# cypi.net
KiCad netlist of a schematic drawn in EAGLE
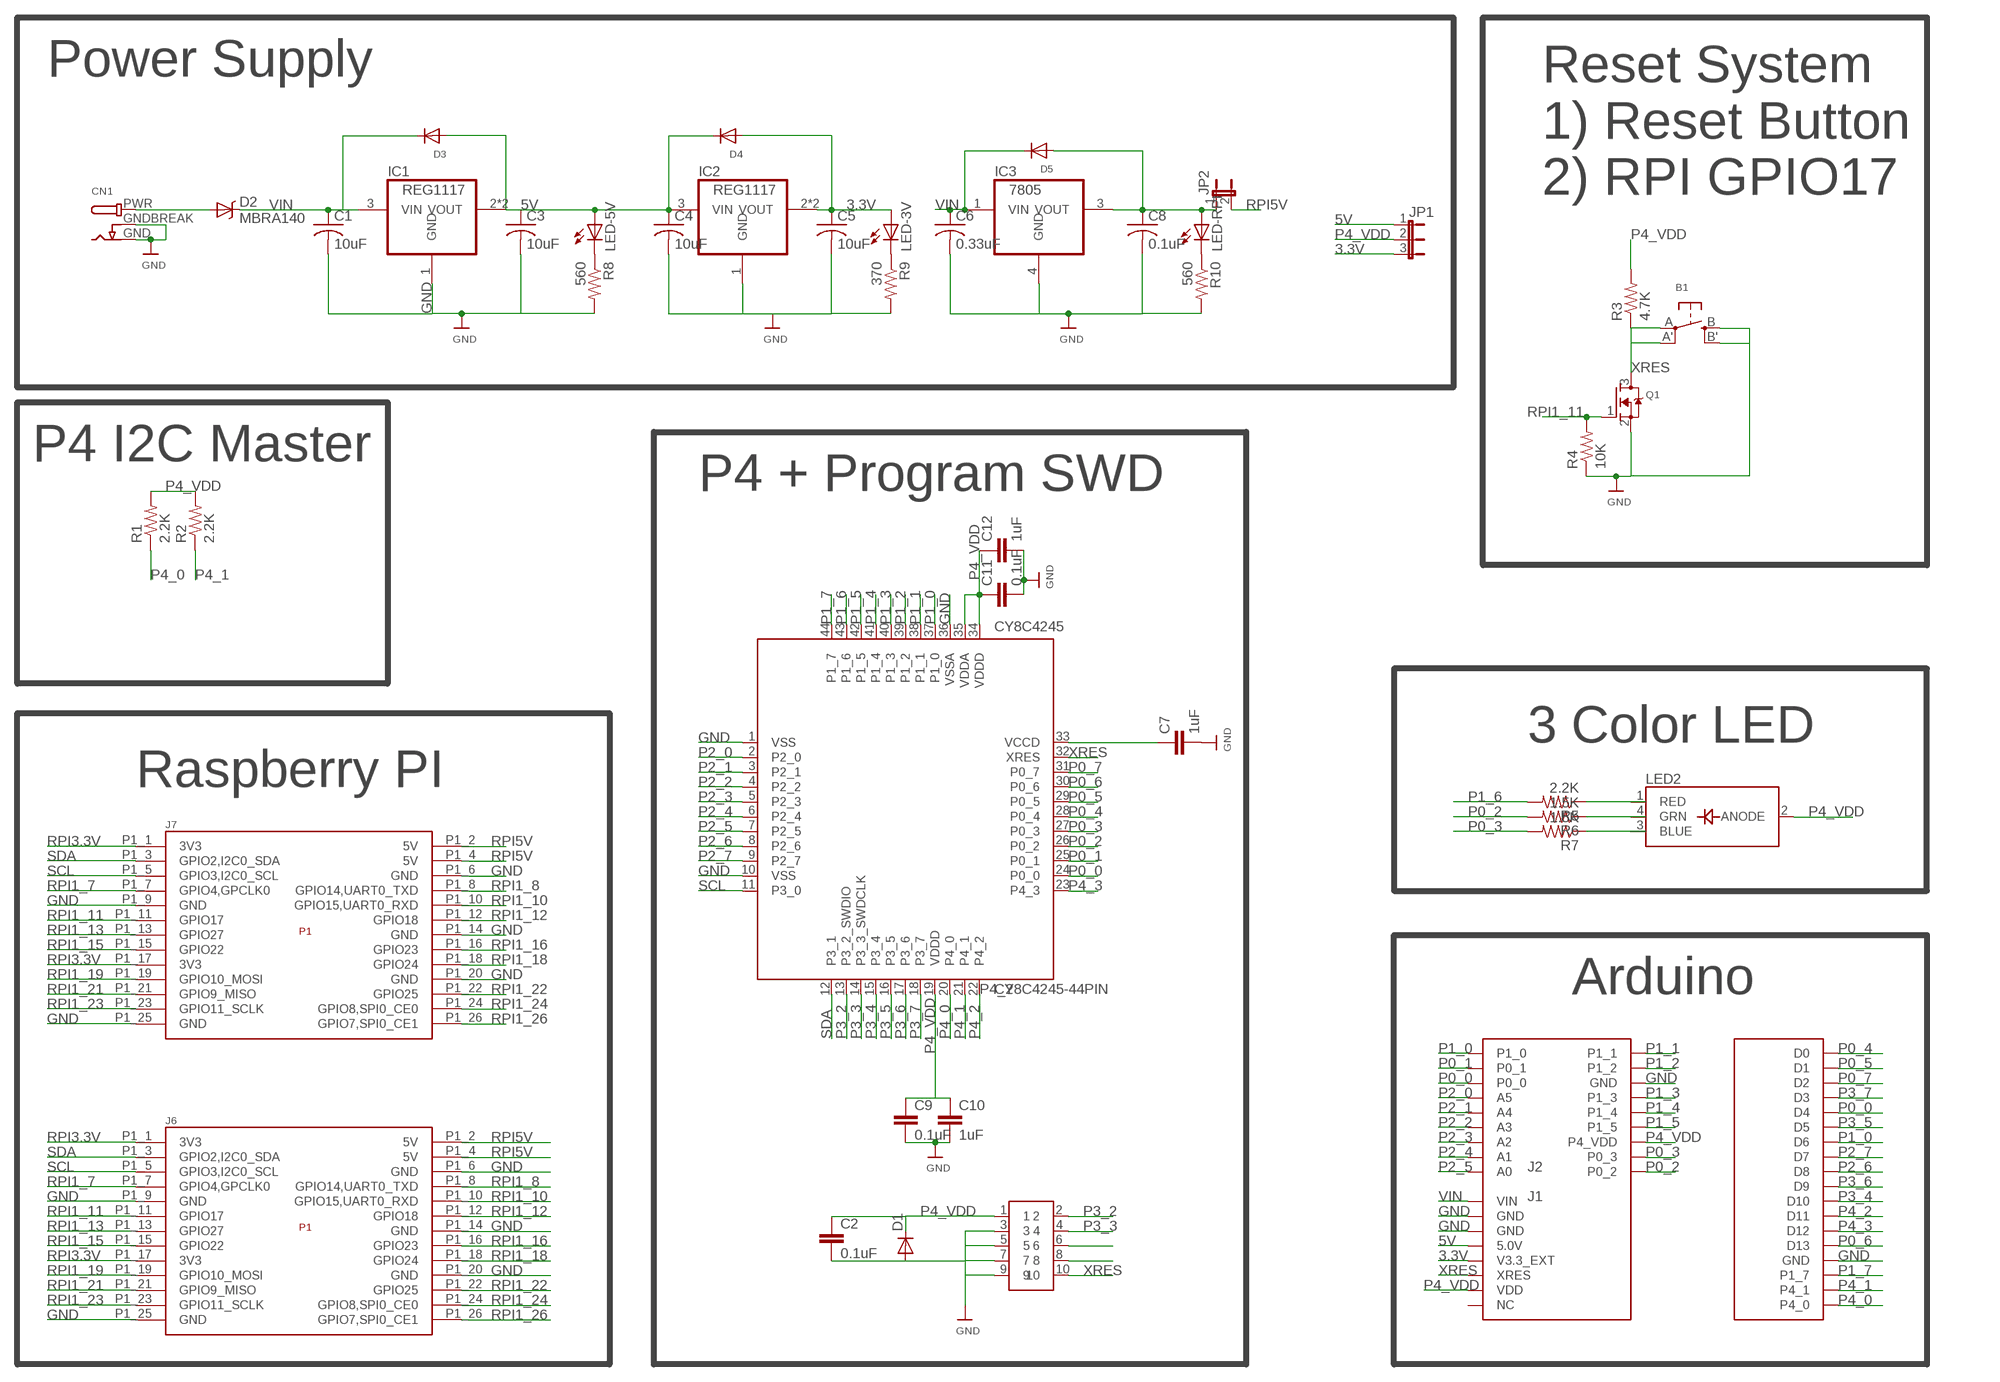
[diagram p0: schematic, sheet 1]

(export (version "E")
  (design (tool "Eeschema 10.0.6"))
  (components
    (comp (ref "B1")
      (value "SWITCH_TACT_SMT")
      (footprint "eagle-import:EVQ-Q2")
      (libsource (lib "eagle-import") (part "SWITCH_TACT_SMT"))
    )
    (comp (ref "C1")
      (value "10uF")
      (footprint "eagle-import:C0805")
      (libsource (lib "eagle-import") (part "C-USC0805"))
    )
    (comp (ref "C2")
      (value "0.1uF")
      (footprint "eagle-import:1206")
      (libsource (lib "eagle-import") (part "CAP1206"))
    )
    (comp (ref "C3")
      (value "10uF")
      (footprint "eagle-import:C0805")
      (libsource (lib "eagle-import") (part "C-USC0805"))
    )
    (comp (ref "C4")
      (value "10uF")
      (footprint "eagle-import:C0805")
      (libsource (lib "eagle-import") (part "C-USC0805"))
    )
    (comp (ref "C5")
      (value "10uF")
      (footprint "eagle-import:C0805")
      (libsource (lib "eagle-import") (part "C-USC0805"))
    )
    (comp (ref "C6")
      (value "0.33uF")
      (footprint "eagle-import:C0805")
      (libsource (lib "eagle-import") (part "C-USC0805"))
    )
    (comp (ref "C7")
      (value "1uF")
      (footprint "eagle-import:1206")
      (libsource (lib "eagle-import") (part "CAP1206"))
    )
    (comp (ref "C8")
      (value "0.1uF")
      (footprint "eagle-import:C0805")
      (libsource (lib "eagle-import") (part "C-USC0805"))
    )
    (comp (ref "C9")
      (value "0.1uF")
      (footprint "eagle-import:1206")
      (libsource (lib "eagle-import") (part "CAP1206"))
    )
    (comp (ref "C10")
      (value "1uF")
      (footprint "eagle-import:1206")
      (libsource (lib "eagle-import") (part "CAP1206"))
    )
    (comp (ref "C11")
      (value "0.1uF")
      (footprint "eagle-import:1206")
      (libsource (lib "eagle-import") (part "CAP1206"))
    )
    (comp (ref "C12")
      (value "1uF")
      (footprint "eagle-import:1206")
      (libsource (lib "eagle-import") (part "CAP1206"))
    )
    (comp (ref "CN1")
      (value "DCBARRELPTH")
      (footprint "eagle-import:DCJACK_2MM_PTH")
      (libsource (lib "eagle-import") (part "DCBARRELPTH"))
    )
    (comp (ref "CY8C4245")
      (value "CY8C4245-44PIN")
      (footprint "eagle-import:TQFP-10X10-44")
      (libsource (lib "eagle-import") (part "CY8C4245-44PIN"))
    )
    (comp (ref "D1")
      (value "DIODEHV")
      (footprint "eagle-import:DIODE-HV")
      (libsource (lib "eagle-import") (part "DIODEHV"))
    )
    (comp (ref "D2")
      (value "MBRA140")
      (footprint "eagle-import:SMA-DIODE")
      (libsource (lib "eagle-import") (part "MBRA140"))
    )
    (comp (ref "D3")
      (value "DIODESOD-123")
      (footprint "eagle-import:SOD-123")
      (libsource (lib "eagle-import") (part "DIODESOD-123"))
    )
    (comp (ref "D4")
      (value "DIODESOD-123")
      (footprint "eagle-import:SOD-123")
      (libsource (lib "eagle-import") (part "DIODESOD-123"))
    )
    (comp (ref "D5")
      (value "DIODESOD-123")
      (footprint "eagle-import:SOD-123")
      (libsource (lib "eagle-import") (part "DIODESOD-123"))
    )
    (comp (ref "IC1")
      (value "REG1117")
      (footprint "eagle-import:SOT223")
      (libsource (lib "eagle-import") (part "REG1117"))
    )
    (comp (ref "IC2")
      (value "REG1117")
      (footprint "eagle-import:SOT223")
      (fields
        (field (name "MPN") "REG1117")
        (field (name "OC_FARNELL") "1097566")
        (field (name "OC_NEWARK") "14P6981")
      )
      (libsource (lib "eagle-import") (part "REG1117"))
    )
    (comp (ref "IC3")
      (value "7805")
      (footprint "eagle-import:DPAK")
      (libsource (lib "eagle-import") (part "7805"))
    )
    (comp (ref "J5")
      (value "SAMTEC")
      (footprint "eagle-import:FTSH-105-01-XXX-DV-K")
      (libsource (lib "eagle-import") (part "SAMTEC"))
    )
    (comp (ref "J6")
      (value "RASPBERRY-PI_REV2PINONLY")
      (footprint "eagle-import:RPI-PINS")
      (libsource (lib "eagle-import") (part "RASPBERRY-PI_REV2PINONLY"))
    )
    (comp (ref "J7")
      (value "RASPBERRY-PI_REV2")
      (footprint "eagle-import:RASPBERRY-PI_REV2")
      (libsource (lib "eagle-import") (part "RASPBERRY-PI_REV2"))
    )
    (comp (ref "JP1")
      (value "JP2E")
      (footprint "eagle-import:JP2")
      (libsource (lib "eagle-import") (part "JP2E"))
    )
    (comp (ref "JP2")
      (value "JUMPER-2PTH")
      (footprint "eagle-import:1X02")
      (libsource (lib "eagle-import") (part "JUMPER-2PTH"))
    )
    (comp (ref "LED-3V")
      (value "LEDCHIPLED_0805")
      (footprint "eagle-import:CHIPLED_0805")
      (libsource (lib "eagle-import") (part "LEDCHIPLED_0805"))
    )
    (comp (ref "LED-5V")
      (value "LEDCHIPLED_0805")
      (footprint "eagle-import:CHIPLED_0805")
      (libsource (lib "eagle-import") (part "LEDCHIPLED_0805"))
    )
    (comp (ref "LED-RPI")
      (value "LEDCHIPLED_0805")
      (footprint "eagle-import:CHIPLED_0805")
      (libsource (lib "eagle-import") (part "LEDCHIPLED_0805"))
    )
    (comp (ref "LED2")
      (value "LED_RGB_PLCC4")
      (footprint "eagle-import:RGBLED_PLCC4")
      (libsource (lib "eagle-import") (part "LED_RGB_PLCC4"))
    )
    (comp (ref "Q1")
      (value "MOSFET-NREFLOW")
      (footprint "eagle-import:SOT23-R")
      (libsource (lib "eagle-import") (part "MOSFET-NREFLOW"))
    )
    (comp (ref "R1")
      (value "2.2K")
      (footprint "eagle-import:0805")
      (libsource (lib "eagle-import") (part "RESISTOR0805-RES"))
    )
    (comp (ref "R2")
      (value "2.2K")
      (footprint "eagle-import:0805")
      (libsource (lib "eagle-import") (part "RESISTOR0805-RES"))
    )
    (comp (ref "R3")
      (value "4.7K")
      (footprint "eagle-import:0805")
      (libsource (lib "eagle-import") (part "RESISTOR0805-RES"))
    )
    (comp (ref "R4")
      (value "10K")
      (footprint "eagle-import:0805")
      (libsource (lib "eagle-import") (part "RESISTOR0805-RES"))
    )
    (comp (ref "R5")
      (value "2.2K")
      (footprint "eagle-import:0805")
      (libsource (lib "eagle-import") (part "RESISTOR0805-RES"))
    )
    (comp (ref "R6")
      (value "1.5K")
      (footprint "eagle-import:0805")
      (libsource (lib "eagle-import") (part "RESISTOR0805-RES"))
    )
    (comp (ref "R7")
      (value "1.5K")
      (footprint "eagle-import:0805")
      (libsource (lib "eagle-import") (part "RESISTOR0805-RES"))
    )
    (comp (ref "R8")
      (value "560")
      (footprint "eagle-import:0805")
      (libsource (lib "eagle-import") (part "RESISTOR0805-RES"))
    )
    (comp (ref "R9")
      (value "370")
      (footprint "eagle-import:0805")
      (libsource (lib "eagle-import") (part "RESISTOR0805-RES"))
    )
    (comp (ref "R10")
      (value "560")
      (footprint "eagle-import:0805")
      (libsource (lib "eagle-import") (part "RESISTOR0805-RES"))
    )
    (comp (ref "U1")
      (value "PIONEERNO_SILK")
      (footprint "eagle-import:PIONEER")
      (libsource (lib "eagle-import") (part "PIONEERNO_SILK"))
    )
  )
  (nets
    (net (code "1") (name "/3.3V") (class "Default")
      (node (ref "C5") (pin "1") (pinfunction "1_1") (pintype "passive"))
      (node (ref "D4") (pin "A") (pinfunction "A_A") (pintype "passive"))
      (node (ref "IC2") (pin "2") (pinfunction "VOUT_2") (pintype "output"))
      (node (ref "IC2") (pin "4") (pinfunction "VOUT_4") (pintype "output"))
      (node (ref "JP1") (pin "3") (pinfunction "3_3") (pintype "passive"))
      (node (ref "LED-3V") (pin "A") (pinfunction "A_A") (pintype "passive"))
      (node (ref "U1") (pin "3.3V") (pinfunction "V3.3_EXT_3.3V") (pintype "bidirectional"))
    )
    (net (code "2") (name "/5V") (class "Default")
      (node (ref "C3") (pin "1") (pinfunction "1_1") (pintype "passive"))
      (node (ref "C4") (pin "1") (pinfunction "1_1") (pintype "passive"))
      (node (ref "D3") (pin "A") (pinfunction "A_A") (pintype "passive"))
      (node (ref "D4") (pin "C") (pinfunction "C_C") (pintype "passive"))
      (node (ref "IC1") (pin "2") (pinfunction "VOUT_2") (pintype "output"))
      (node (ref "IC1") (pin "4") (pinfunction "VOUT_4") (pintype "output"))
      (node (ref "IC2") (pin "3") (pinfunction "VIN_3") (pintype "input"))
      (node (ref "JP1") (pin "1") (pinfunction "1_1") (pintype "passive"))
      (node (ref "LED-5V") (pin "A") (pinfunction "A_A") (pintype "passive"))
      (node (ref "U1") (pin "5V") (pinfunction "5.0V_5V") (pintype "bidirectional"))
    )
    (net (code "3") (name "/P0_0") (class "Default")
      (node (ref "CY8C4245") (pin "24") (pinfunction "P0_0_24") (pintype "bidirectional"))
      (node (ref "U1") (pin "D4") (pinfunction "D4_D4") (pintype "bidirectional"))
      (node (ref "U1") (pin "P0_0") (pinfunction "P0_0_P0_0") (pintype "bidirectional"))
    )
    (net (code "4") (name "/P0_1") (class "Default")
      (node (ref "CY8C4245") (pin "25") (pinfunction "P0_1_25") (pintype "bidirectional"))
      (node (ref "U1") (pin "P0_1") (pinfunction "P0_1_P0_1") (pintype "bidirectional"))
    )
    (net (code "5") (name "/P0_2") (class "Default")
      (node (ref "CY8C4245") (pin "26") (pinfunction "P0_2_26") (pintype "input"))
      (node (ref "R6") (pin "2") (pinfunction "2_2") (pintype "passive"))
      (node (ref "U1") (pin "P0_2") (pinfunction "P0_2_P0_2") (pintype "bidirectional"))
    )
    (net (code "6") (name "/P0_3") (class "Default")
      (node (ref "CY8C4245") (pin "27") (pinfunction "P0_3_27") (pintype "bidirectional"))
      (node (ref "R7") (pin "2") (pinfunction "2_2") (pintype "passive"))
      (node (ref "U1") (pin "P0_3") (pinfunction "P0_3_P0_3") (pintype "bidirectional"))
    )
    (net (code "7") (name "/P0_4") (class "Default")
      (node (ref "CY8C4245") (pin "28") (pinfunction "P0_4_28") (pintype "bidirectional"))
      (node (ref "U1") (pin "D0") (pinfunction "D0_D0") (pintype "bidirectional"))
    )
    (net (code "8") (name "/P0_5") (class "Default")
      (node (ref "CY8C4245") (pin "29") (pinfunction "P0_5_29") (pintype "bidirectional"))
      (node (ref "U1") (pin "D1") (pinfunction "D1_D1") (pintype "bidirectional"))
    )
    (net (code "9") (name "/P0_6") (class "Default")
      (node (ref "CY8C4245") (pin "30") (pinfunction "P0_6_30") (pintype "power_in"))
      (node (ref "U1") (pin "D13") (pinfunction "D13_D13") (pintype "bidirectional"))
    )
    (net (code "10") (name "/P0_7") (class "Default")
      (node (ref "CY8C4245") (pin "31") (pinfunction "P0_7_31") (pintype "bidirectional"))
      (node (ref "U1") (pin "D2") (pinfunction "D2_D2") (pintype "bidirectional"))
    )
    (net (code "11") (name "/P1_0") (class "Default")
      (node (ref "CY8C4245") (pin "37") (pinfunction "P1_0_37") (pintype "bidirectional"))
      (node (ref "U1") (pin "D6") (pinfunction "D6_D6") (pintype "bidirectional"))
      (node (ref "U1") (pin "P1_0") (pinfunction "P1_0_P1_0") (pintype "bidirectional"))
    )
    (net (code "12") (name "/P1_1") (class "Default")
      (node (ref "CY8C4245") (pin "38") (pinfunction "P1_1_38") (pintype "bidirectional"))
      (node (ref "U1") (pin "P1_1") (pinfunction "P1_1_P1_1") (pintype "bidirectional"))
    )
    (net (code "13") (name "/P1_2") (class "Default")
      (node (ref "CY8C4245") (pin "39") (pinfunction "P1_2_39") (pintype "power_in"))
      (node (ref "U1") (pin "P1_2") (pinfunction "P1_2_P1_2") (pintype "bidirectional"))
    )
    (net (code "14") (name "/P1_3") (class "Default")
      (node (ref "CY8C4245") (pin "40") (pinfunction "P1_3_40") (pintype "bidirectional"))
      (node (ref "U1") (pin "P1_3") (pinfunction "P1_3_P1_3") (pintype "bidirectional"))
    )
    (net (code "15") (name "/P1_4") (class "Default")
      (node (ref "CY8C4245") (pin "41") (pinfunction "P1_4_41") (pintype "bidirectional"))
      (node (ref "U1") (pin "P1_4") (pinfunction "P1_4_P1_4") (pintype "bidirectional"))
    )
    (net (code "16") (name "/P1_5") (class "Default")
      (node (ref "CY8C4245") (pin "42") (pinfunction "P1_5_42") (pintype "bidirectional"))
      (node (ref "U1") (pin "P1_5") (pinfunction "P1_5_P1_5") (pintype "bidirectional"))
    )
    (net (code "17") (name "/P1_6") (class "Default")
      (node (ref "CY8C4245") (pin "43") (pinfunction "P1_6_43") (pintype "bidirectional"))
      (node (ref "R5") (pin "2") (pinfunction "2_2") (pintype "passive"))
    )
    (net (code "18") (name "/P1_7") (class "Default")
      (node (ref "CY8C4245") (pin "44") (pinfunction "P1_7_44") (pintype "bidirectional"))
      (node (ref "U1") (pin "AREF") (pinfunction "P1_7_AREF") (pintype "bidirectional"))
    )
    (net (code "19") (name "/P2_0") (class "Default")
      (node (ref "CY8C4245") (pin "2") (pinfunction "P2_0_2") (pintype "bidirectional"))
      (node (ref "U1") (pin "A0") (pinfunction "A5_A0") (pintype "bidirectional"))
    )
    (net (code "20") (name "/P2_1") (class "Default")
      (node (ref "CY8C4245") (pin "3") (pinfunction "P2_1_3") (pintype "bidirectional"))
      (node (ref "U1") (pin "A1") (pinfunction "A4_A1") (pintype "bidirectional"))
    )
    (net (code "21") (name "/P2_2") (class "Default")
      (node (ref "CY8C4245") (pin "4") (pinfunction "P2_2_4") (pintype "power_in"))
      (node (ref "U1") (pin "A2") (pinfunction "A3_A2") (pintype "bidirectional"))
    )
    (net (code "22") (name "/P2_3") (class "Default")
      (node (ref "CY8C4245") (pin "5") (pinfunction "P2_3_5") (pintype "bidirectional"))
      (node (ref "U1") (pin "A3") (pinfunction "A2_A3") (pintype "bidirectional"))
    )
    (net (code "23") (name "/P2_4") (class "Default")
      (node (ref "CY8C4245") (pin "6") (pinfunction "P2_4_6") (pintype "bidirectional"))
      (node (ref "U1") (pin "A4") (pinfunction "A1_A4") (pintype "bidirectional"))
    )
    (net (code "24") (name "/P2_5") (class "Default")
      (node (ref "CY8C4245") (pin "7") (pinfunction "P2_5_7") (pintype "bidirectional"))
      (node (ref "U1") (pin "A5") (pinfunction "A0_A5") (pintype "bidirectional"))
    )
    (net (code "25") (name "/P2_6") (class "Default")
      (node (ref "CY8C4245") (pin "8") (pinfunction "P2_6_8") (pintype "power_in"))
      (node (ref "U1") (pin "D8") (pinfunction "D8_D8") (pintype "bidirectional"))
    )
    (net (code "26") (name "/P2_7") (class "Default")
      (node (ref "CY8C4245") (pin "9") (pinfunction "P2_7_9") (pintype "bidirectional"))
      (node (ref "U1") (pin "D7") (pinfunction "D7_D7") (pintype "bidirectional"))
    )
    (net (code "27") (name "/P3_2") (class "Default")
      (node (ref "CY8C4245") (pin "13") (pinfunction "P3_2_SWDIO_13") (pintype "bidirectional"))
      (node (ref "J5") (pin "2") (pinfunction "2_2") (pintype "bidirectional"))
    )
    (net (code "28") (name "/P3_3") (class "Default")
      (node (ref "CY8C4245") (pin "14") (pinfunction "P3_3_SWDCLK_14") (pintype "bidirectional"))
      (node (ref "J5") (pin "4") (pinfunction "4_4") (pintype "bidirectional"))
    )
    (net (code "29") (name "/P3_4") (class "Default")
      (node (ref "CY8C4245") (pin "15") (pinfunction "P3_4_15") (pintype "bidirectional"))
      (node (ref "U1") (pin "D10") (pinfunction "D10_D10") (pintype "bidirectional"))
    )
    (net (code "30") (name "/P3_5") (class "Default")
      (node (ref "CY8C4245") (pin "16") (pinfunction "P3_5_16") (pintype "bidirectional"))
      (node (ref "U1") (pin "D5") (pinfunction "D5_D5") (pintype "bidirectional"))
    )
    (net (code "31") (name "/P3_6") (class "Default")
      (node (ref "CY8C4245") (pin "17") (pinfunction "P3_6_17") (pintype "power_in"))
      (node (ref "U1") (pin "D9") (pinfunction "D9_D9") (pintype "bidirectional"))
    )
    (net (code "32") (name "/P3_7") (class "Default")
      (node (ref "CY8C4245") (pin "18") (pinfunction "P3_7_18") (pintype "bidirectional"))
      (node (ref "U1") (pin "D3") (pinfunction "D3_D3") (pintype "bidirectional"))
    )
    (net (code "33") (name "/P4_0") (class "Default")
      (node (ref "CY8C4245") (pin "20") (pinfunction "P4_0_20") (pintype "bidirectional"))
      (node (ref "R1") (pin "1") (pinfunction "1_1") (pintype "passive"))
      (node (ref "U1") (pin "SCL") (pinfunction "P4_0_SCL") (pintype "bidirectional"))
    )
    (net (code "34") (name "/P4_1") (class "Default")
      (node (ref "CY8C4245") (pin "21") (pinfunction "P4_1_21") (pintype "bidirectional"))
      (node (ref "R2") (pin "1") (pinfunction "1_1") (pintype "passive"))
      (node (ref "U1") (pin "SDA") (pinfunction "P4_1_SDA") (pintype "bidirectional"))
    )
    (net (code "35") (name "/P4_2") (class "Default")
      (node (ref "CY8C4245") (pin "22") (pinfunction "P4_2_22") (pintype "bidirectional"))
      (node (ref "U1") (pin "D11") (pinfunction "D11_D11") (pintype "bidirectional"))
    )
    (net (code "36") (name "/P4_3") (class "Default")
      (node (ref "CY8C4245") (pin "23") (pinfunction "P4_3_23") (pintype "bidirectional"))
      (node (ref "U1") (pin "D12") (pinfunction "D12_D12") (pintype "bidirectional"))
    )
    (net (code "37") (name "/P4_VDD") (class "Default")
      (node (ref "C10") (pin "1") (pinfunction "1_1") (pintype "passive"))
      (node (ref "C11") (pin "1") (pinfunction "1_1") (pintype "passive"))
      (node (ref "C12") (pin "1") (pinfunction "1_1") (pintype "passive"))
      (node (ref "C2") (pin "1") (pinfunction "1_1") (pintype "passive"))
      (node (ref "C9") (pin "1") (pinfunction "1_1") (pintype "passive"))
      (node (ref "CY8C4245") (pin "19") (pinfunction "VDDD_19") (pintype "bidirectional"))
      (node (ref "CY8C4245") (pin "34") (pinfunction "VDDD_34") (pintype "bidirectional"))
      (node (ref "CY8C4245") (pin "35") (pinfunction "VDDA_35") (pintype "bidirectional"))
      (node (ref "D1") (pin "C") (pinfunction "C_C") (pintype "passive"))
      (node (ref "J5") (pin "1") (pinfunction "1_1") (pintype "bidirectional"))
      (node (ref "JP1") (pin "2") (pinfunction "2_2") (pintype "passive"))
      (node (ref "LED2") (pin "2") (pinfunction "ANODE_2") (pintype "power_in"))
      (node (ref "R1") (pin "2") (pinfunction "2_2") (pintype "passive"))
      (node (ref "R2") (pin "2") (pinfunction "2_2") (pintype "passive"))
      (node (ref "R3") (pin "2") (pinfunction "2_2") (pintype "passive"))
      (node (ref "U1") (pin "P4_VDD") (pinfunction "P4_VDD_P4_VDD") (pintype "bidirectional"))
      (node (ref "U1") (pin "P4_VDD1") (pinfunction "VDD_P4_VDD1") (pintype "bidirectional"))
    )
    (net (code "38") (name "/RPI1_7") (class "Default")
      (node (ref "J6") (pin "P1_7") (pinfunction "GPIO4,GPCLK0_P1_7") (pintype "bidirectional"))
      (node (ref "J7") (pin "P1_7") (pinfunction "GPIO4,GPCLK0_P1_7") (pintype "bidirectional"))
    )
    (net (code "39") (name "/RPI1_8") (class "Default")
      (node (ref "J6") (pin "P1_8") (pinfunction "GPIO14,UART0_TXD_P1_8") (pintype "bidirectional"))
      (node (ref "J7") (pin "P1_8") (pinfunction "GPIO14,UART0_TXD_P1_8") (pintype "bidirectional"))
    )
    (net (code "40") (name "/RPI1_10") (class "Default")
      (node (ref "J6") (pin "P1_10") (pinfunction "GPIO15,UART0_RXD_P1_10") (pintype "bidirectional"))
      (node (ref "J7") (pin "P1_10") (pinfunction "GPIO15,UART0_RXD_P1_10") (pintype "bidirectional"))
    )
    (net (code "41") (name "/RPI1_11") (class "Default")
      (node (ref "J6") (pin "P1_11") (pinfunction "GPIO17_P1_11") (pintype "bidirectional"))
      (node (ref "J7") (pin "P1_11") (pinfunction "GPIO17_P1_11") (pintype "bidirectional"))
      (node (ref "Q1") (pin "1") (pinfunction "G_1") (pintype "bidirectional"))
      (node (ref "R4") (pin "2") (pinfunction "2_2") (pintype "passive"))
    )
    (net (code "42") (name "/RPI1_12") (class "Default")
      (node (ref "J6") (pin "P1_12") (pinfunction "GPIO18_P1_12") (pintype "bidirectional"))
      (node (ref "J7") (pin "P1_12") (pinfunction "GPIO18_P1_12") (pintype "bidirectional"))
    )
    (net (code "43") (name "/RPI1_13") (class "Default")
      (node (ref "J6") (pin "P1_13") (pinfunction "GPIO27_P1_13") (pintype "bidirectional"))
      (node (ref "J7") (pin "P1_13") (pinfunction "GPIO27_P1_13") (pintype "bidirectional"))
    )
    (net (code "44") (name "/RPI1_15") (class "Default")
      (node (ref "J6") (pin "P1_15") (pinfunction "GPIO22_P1_15") (pintype "bidirectional"))
      (node (ref "J7") (pin "P1_15") (pinfunction "GPIO22_P1_15") (pintype "bidirectional"))
    )
    (net (code "45") (name "/RPI1_16") (class "Default")
      (node (ref "J6") (pin "P1_16") (pinfunction "GPIO23_P1_16") (pintype "bidirectional"))
      (node (ref "J7") (pin "P1_16") (pinfunction "GPIO23_P1_16") (pintype "bidirectional"))
    )
    (net (code "46") (name "/RPI1_18") (class "Default")
      (node (ref "J6") (pin "P1_18") (pinfunction "GPIO24_P1_18") (pintype "bidirectional"))
      (node (ref "J7") (pin "P1_18") (pinfunction "GPIO24_P1_18") (pintype "bidirectional"))
    )
    (net (code "47") (name "/RPI1_19") (class "Default")
      (node (ref "J6") (pin "P1_19") (pinfunction "GPIO10_MOSI_P1_19") (pintype "bidirectional"))
      (node (ref "J7") (pin "P1_19") (pinfunction "GPIO10_MOSI_P1_19") (pintype "bidirectional"))
    )
    (net (code "48") (name "/RPI1_21") (class "Default")
      (node (ref "J6") (pin "P1_21") (pinfunction "GPIO9_MISO_P1_21") (pintype "bidirectional"))
      (node (ref "J7") (pin "P1_21") (pinfunction "GPIO9_MISO_P1_21") (pintype "bidirectional"))
    )
    (net (code "49") (name "/RPI1_22") (class "Default")
      (node (ref "J6") (pin "P1_22") (pinfunction "GPIO25_P1_22") (pintype "bidirectional"))
      (node (ref "J7") (pin "P1_22") (pinfunction "GPIO25_P1_22") (pintype "bidirectional"))
    )
    (net (code "50") (name "/RPI1_23") (class "Default")
      (node (ref "J6") (pin "P1_23") (pinfunction "GPIO11_SCLK_P1_23") (pintype "bidirectional"))
      (node (ref "J7") (pin "P1_23") (pinfunction "GPIO11_SCLK_P1_23") (pintype "bidirectional"))
    )
    (net (code "51") (name "/RPI1_24") (class "Default")
      (node (ref "J6") (pin "P1_24") (pinfunction "GPIO8,SPI0_CE0_P1_24") (pintype "bidirectional"))
      (node (ref "J7") (pin "P1_24") (pinfunction "GPIO8,SPI0_CE0_P1_24") (pintype "bidirectional"))
    )
    (net (code "52") (name "/RPI1_26") (class "Default")
      (node (ref "J6") (pin "P1_26") (pinfunction "GPIO7,SPI0_CE1_P1_26") (pintype "bidirectional"))
      (node (ref "J7") (pin "P1_26") (pinfunction "GPIO7,SPI0_CE1_P1_26") (pintype "bidirectional"))
    )
    (net (code "53") (name "/RPI3.3V") (class "Default")
      (node (ref "J6") (pin "P1_1") (pinfunction "3V3_P1_1") (pintype "bidirectional"))
      (node (ref "J6") (pin "P1_17") (pinfunction "3V3_P1_17") (pintype "bidirectional"))
      (node (ref "J7") (pin "P1_1") (pinfunction "3V3_P1_1") (pintype "bidirectional"))
      (node (ref "J7") (pin "P1_17") (pinfunction "3V3_P1_17") (pintype "bidirectional"))
    )
    (net (code "54") (name "/RPI5V") (class "Default")
      (node (ref "J6") (pin "P1_2") (pinfunction "5V_P1_2") (pintype "bidirectional"))
      (node (ref "J6") (pin "P1_4") (pinfunction "5V_P1_4") (pintype "bidirectional"))
      (node (ref "J7") (pin "P1_2") (pinfunction "5V_P1_2") (pintype "bidirectional"))
      (node (ref "J7") (pin "P1_4") (pinfunction "5V_P1_4") (pintype "bidirectional"))
      (node (ref "JP2") (pin "2") (pinfunction "2_2") (pintype "passive"))
    )
    (net (code "55") (name "/SCL") (class "Default")
      (node (ref "CY8C4245") (pin "11") (pinfunction "P3_0_11") (pintype "bidirectional"))
      (node (ref "J6") (pin "P1_5") (pinfunction "GPIO3,I2C0_SCL_P1_5") (pintype "bidirectional"))
      (node (ref "J7") (pin "P1_5") (pinfunction "GPIO3,I2C0_SCL_P1_5") (pintype "bidirectional"))
    )
    (net (code "56") (name "/SDA") (class "Default")
      (node (ref "CY8C4245") (pin "12") (pinfunction "P3_1_12") (pintype "bidirectional"))
      (node (ref "J6") (pin "P1_3") (pinfunction "GPIO2,I2C0_SDA_P1_3") (pintype "bidirectional"))
      (node (ref "J7") (pin "P1_3") (pinfunction "GPIO2,I2C0_SDA_P1_3") (pintype "bidirectional"))
    )
    (net (code "57") (name "/VIN") (class "Default")
      (node (ref "C1") (pin "1") (pinfunction "1_1") (pintype "passive"))
      (node (ref "C6") (pin "1") (pinfunction "1_1") (pintype "passive"))
      (node (ref "D2") (pin "C") (pinfunction "C_C") (pintype "passive"))
      (node (ref "D3") (pin "C") (pinfunction "C_C") (pintype "passive"))
      (node (ref "D5") (pin "C") (pinfunction "C_C") (pintype "passive"))
      (node (ref "IC1") (pin "3") (pinfunction "VIN_3") (pintype "input"))
      (node (ref "IC3") (pin "1") (pinfunction "VIN_1") (pintype "input"))
      (node (ref "U1") (pin "VIN") (pinfunction "VIN_VIN") (pintype "bidirectional"))
    )
    (net (code "58") (name "/XRES") (class "Default")
      (node (ref "B1") (pin "A") (pinfunction "P_A") (pintype "passive"))
      (node (ref "B1") (pin "A'") (pinfunction "P1_A'") (pintype "passive"))
      (node (ref "CY8C4245") (pin "32") (pinfunction "XRES_32") (pintype "bidirectional"))
      (node (ref "J5") (pin "10") (pinfunction "10_10") (pintype "bidirectional"))
      (node (ref "Q1") (pin "3") (pinfunction "D_3") (pintype "bidirectional"))
      (node (ref "R3") (pin "1") (pinfunction "1_1") (pintype "passive"))
      (node (ref "U1") (pin "XRES") (pinfunction "XRES_XRES") (pintype "bidirectional"))
    )
    (net (code "59") (name "GND") (class "Default")
      (node (ref "B1") (pin "B") (pinfunction "S_B") (pintype "passive"))
      (node (ref "B1") (pin "B'") (pinfunction "S1_B'") (pintype "passive"))
      (node (ref "C1") (pin "2") (pinfunction "2_2") (pintype "passive"))
      (node (ref "C10") (pin "2") (pinfunction "2_2") (pintype "passive"))
      (node (ref "C11") (pin "2") (pinfunction "2_2") (pintype "passive"))
      (node (ref "C12") (pin "2") (pinfunction "2_2") (pintype "passive"))
      (node (ref "C2") (pin "2") (pinfunction "2_2") (pintype "passive"))
      (node (ref "C3") (pin "2") (pinfunction "2_2") (pintype "passive"))
      (node (ref "C4") (pin "2") (pinfunction "2_2") (pintype "passive"))
      (node (ref "C5") (pin "2") (pinfunction "2_2") (pintype "passive"))
      (node (ref "C6") (pin "2") (pinfunction "2_2") (pintype "passive"))
      (node (ref "C7") (pin "2") (pinfunction "2_2") (pintype "passive"))
      (node (ref "C8") (pin "2") (pinfunction "2_2") (pintype "passive"))
      (node (ref "C9") (pin "2") (pinfunction "2_2") (pintype "passive"))
      (node (ref "CN1") (pin "GND") (pinfunction "GND_GND") (pintype "power_in"))
      (node (ref "CN1") (pin "GNDBREAK") (pinfunction "GNDBREAK_GNDBREAK") (pintype "power_in"))
      (node (ref "CY8C4245") (pin "1") (pinfunction "VSS_1") (pintype "bidirectional"))
      (node (ref "CY8C4245") (pin "10") (pinfunction "VSS_10") (pintype "bidirectional"))
      (node (ref "CY8C4245") (pin "36") (pinfunction "VSSA_36") (pintype "bidirectional"))
      (node (ref "D1") (pin "A") (pinfunction "A_A") (pintype "passive"))
      (node (ref "IC1") (pin "1") (pinfunction "GND_1") (pintype "power_in"))
      (node (ref "IC2") (pin "1") (pinfunction "GND_1") (pintype "power_in"))
      (node (ref "IC3") (pin "4") (pinfunction "GND_4") (pintype "power_in"))
      (node (ref "J5") (pin "3") (pinfunction "3_3") (pintype "bidirectional"))
      (node (ref "J5") (pin "5") (pinfunction "5_5") (pintype "bidirectional"))
      (node (ref "J5") (pin "7") (pinfunction "7_7") (pintype "bidirectional"))
      (node (ref "J5") (pin "9") (pinfunction "9_9") (pintype "bidirectional"))
      (node (ref "J6") (pin "P1_14") (pinfunction "GND_P1_14") (pintype "bidirectional"))
      (node (ref "J6") (pin "P1_20") (pinfunction "GND_P1_20") (pintype "bidirectional"))
      (node (ref "J6") (pin "P1_25") (pinfunction "GND_P1_25") (pintype "bidirectional"))
      (node (ref "J6") (pin "P1_6") (pinfunction "GND_P1_6") (pintype "bidirectional"))
      (node (ref "J6") (pin "P1_9") (pinfunction "GND_P1_9") (pintype "bidirectional"))
      (node (ref "J7") (pin "P1_14") (pinfunction "GND_P1_14") (pintype "bidirectional"))
      (node (ref "J7") (pin "P1_20") (pinfunction "GND_P1_20") (pintype "bidirectional"))
      (node (ref "J7") (pin "P1_25") (pinfunction "GND_P1_25") (pintype "bidirectional"))
      (node (ref "J7") (pin "P1_6") (pinfunction "GND_P1_6") (pintype "bidirectional"))
      (node (ref "J7") (pin "P1_9") (pinfunction "GND_P1_9") (pintype "bidirectional"))
      (node (ref "Q1") (pin "2") (pinfunction "S_2") (pintype "bidirectional"))
      (node (ref "R10") (pin "2") (pinfunction "2_2") (pintype "passive"))
      (node (ref "R4") (pin "1") (pinfunction "1_1") (pintype "passive"))
      (node (ref "R8") (pin "2") (pinfunction "2_2") (pintype "passive"))
      (node (ref "R9") (pin "2") (pinfunction "2_2") (pintype "passive"))
      (node (ref "U1") (pin "GND@2") (pinfunction "GND_GND@2") (pintype "bidirectional"))
      (node (ref "U1") (pin "GND@3") (pinfunction "GND_GND@3") (pintype "bidirectional"))
      (node (ref "U1") (pin "GND@3R") (pinfunction "GND_GND@3R") (pintype "bidirectional"))
      (node (ref "U1") (pin "GND@7") (pinfunction "GND_GND@7") (pintype "bidirectional"))
    )
    (net (code "60") (name "Net-(CN1-PadPWR)") (class "Default")
      (node (ref "CN1") (pin "PWR") (pinfunction "PWR_PWR") (pintype "power_in"))
      (node (ref "D2") (pin "A") (pinfunction "A_A") (pintype "passive"))
    )
    (net (code "61") (name "Net-(CY8C4245-VCCD)") (class "Default")
      (node (ref "C7") (pin "1") (pinfunction "1_1") (pintype "passive"))
      (node (ref "CY8C4245") (pin "33") (pinfunction "VCCD_33") (pintype "bidirectional"))
    )
    (net (code "62") (name "Net-(IC3-VOUT)") (class "Default")
      (node (ref "C8") (pin "1") (pinfunction "1_1") (pintype "passive"))
      (node (ref "D5") (pin "A") (pinfunction "A_A") (pintype "passive"))
      (node (ref "IC3") (pin "3") (pinfunction "VOUT_3") (pintype "output"))
      (node (ref "JP2") (pin "1") (pinfunction "1_1") (pintype "passive"))
      (node (ref "LED-RPI") (pin "A") (pinfunction "A_A") (pintype "passive"))
    )
    (net (code "63") (name "Net-(LED-3V-PadC)") (class "Default")
      (node (ref "LED-3V") (pin "C") (pinfunction "C_C") (pintype "passive"))
      (node (ref "R9") (pin "1") (pinfunction "1_1") (pintype "passive"))
    )
    (net (code "64") (name "Net-(LED-5V-PadC)") (class "Default")
      (node (ref "LED-5V") (pin "C") (pinfunction "C_C") (pintype "passive"))
      (node (ref "R8") (pin "1") (pinfunction "1_1") (pintype "passive"))
    )
    (net (code "65") (name "Net-(LED-RPI-PadC)") (class "Default")
      (node (ref "LED-RPI") (pin "C") (pinfunction "C_C") (pintype "passive"))
      (node (ref "R10") (pin "1") (pinfunction "1_1") (pintype "passive"))
    )
    (net (code "66") (name "Net-(LED2-BLUE)") (class "Default")
      (node (ref "LED2") (pin "3") (pinfunction "BLUE_3") (pintype "bidirectional"))
      (node (ref "R7") (pin "1") (pinfunction "1_1") (pintype "passive"))
    )
    (net (code "67") (name "Net-(LED2-GRN)") (class "Default")
      (node (ref "LED2") (pin "4") (pinfunction "GRN_4") (pintype "bidirectional"))
      (node (ref "R6") (pin "1") (pinfunction "1_1") (pintype "passive"))
    )
    (net (code "68") (name "Net-(LED2-RED)") (class "Default")
      (node (ref "LED2") (pin "1") (pinfunction "RED_1") (pintype "bidirectional"))
      (node (ref "R5") (pin "1") (pinfunction "1_1") (pintype "passive"))
    )
    (net (code "69") (name "unconnected-(J5-Pad6)") (class "Default")
      (node (ref "J5") (pin "6") (pinfunction "6_6") (pintype "bidirectional"))
    )
    (net (code "70") (name "unconnected-(J5-Pad8)") (class "Default")
      (node (ref "J5") (pin "8") (pinfunction "8_8") (pintype "bidirectional"))
    )
    (net (code "71") (name "unconnected-(U1-NC-PadNC@8)") (class "Default")
      (node (ref "U1") (pin "NC@8") (pinfunction "NC_NC@8") (pintype "bidirectional"))
    )
  )
)
